# FPGA.net
KiCad netlist of a schematic drawn in Altium Designer
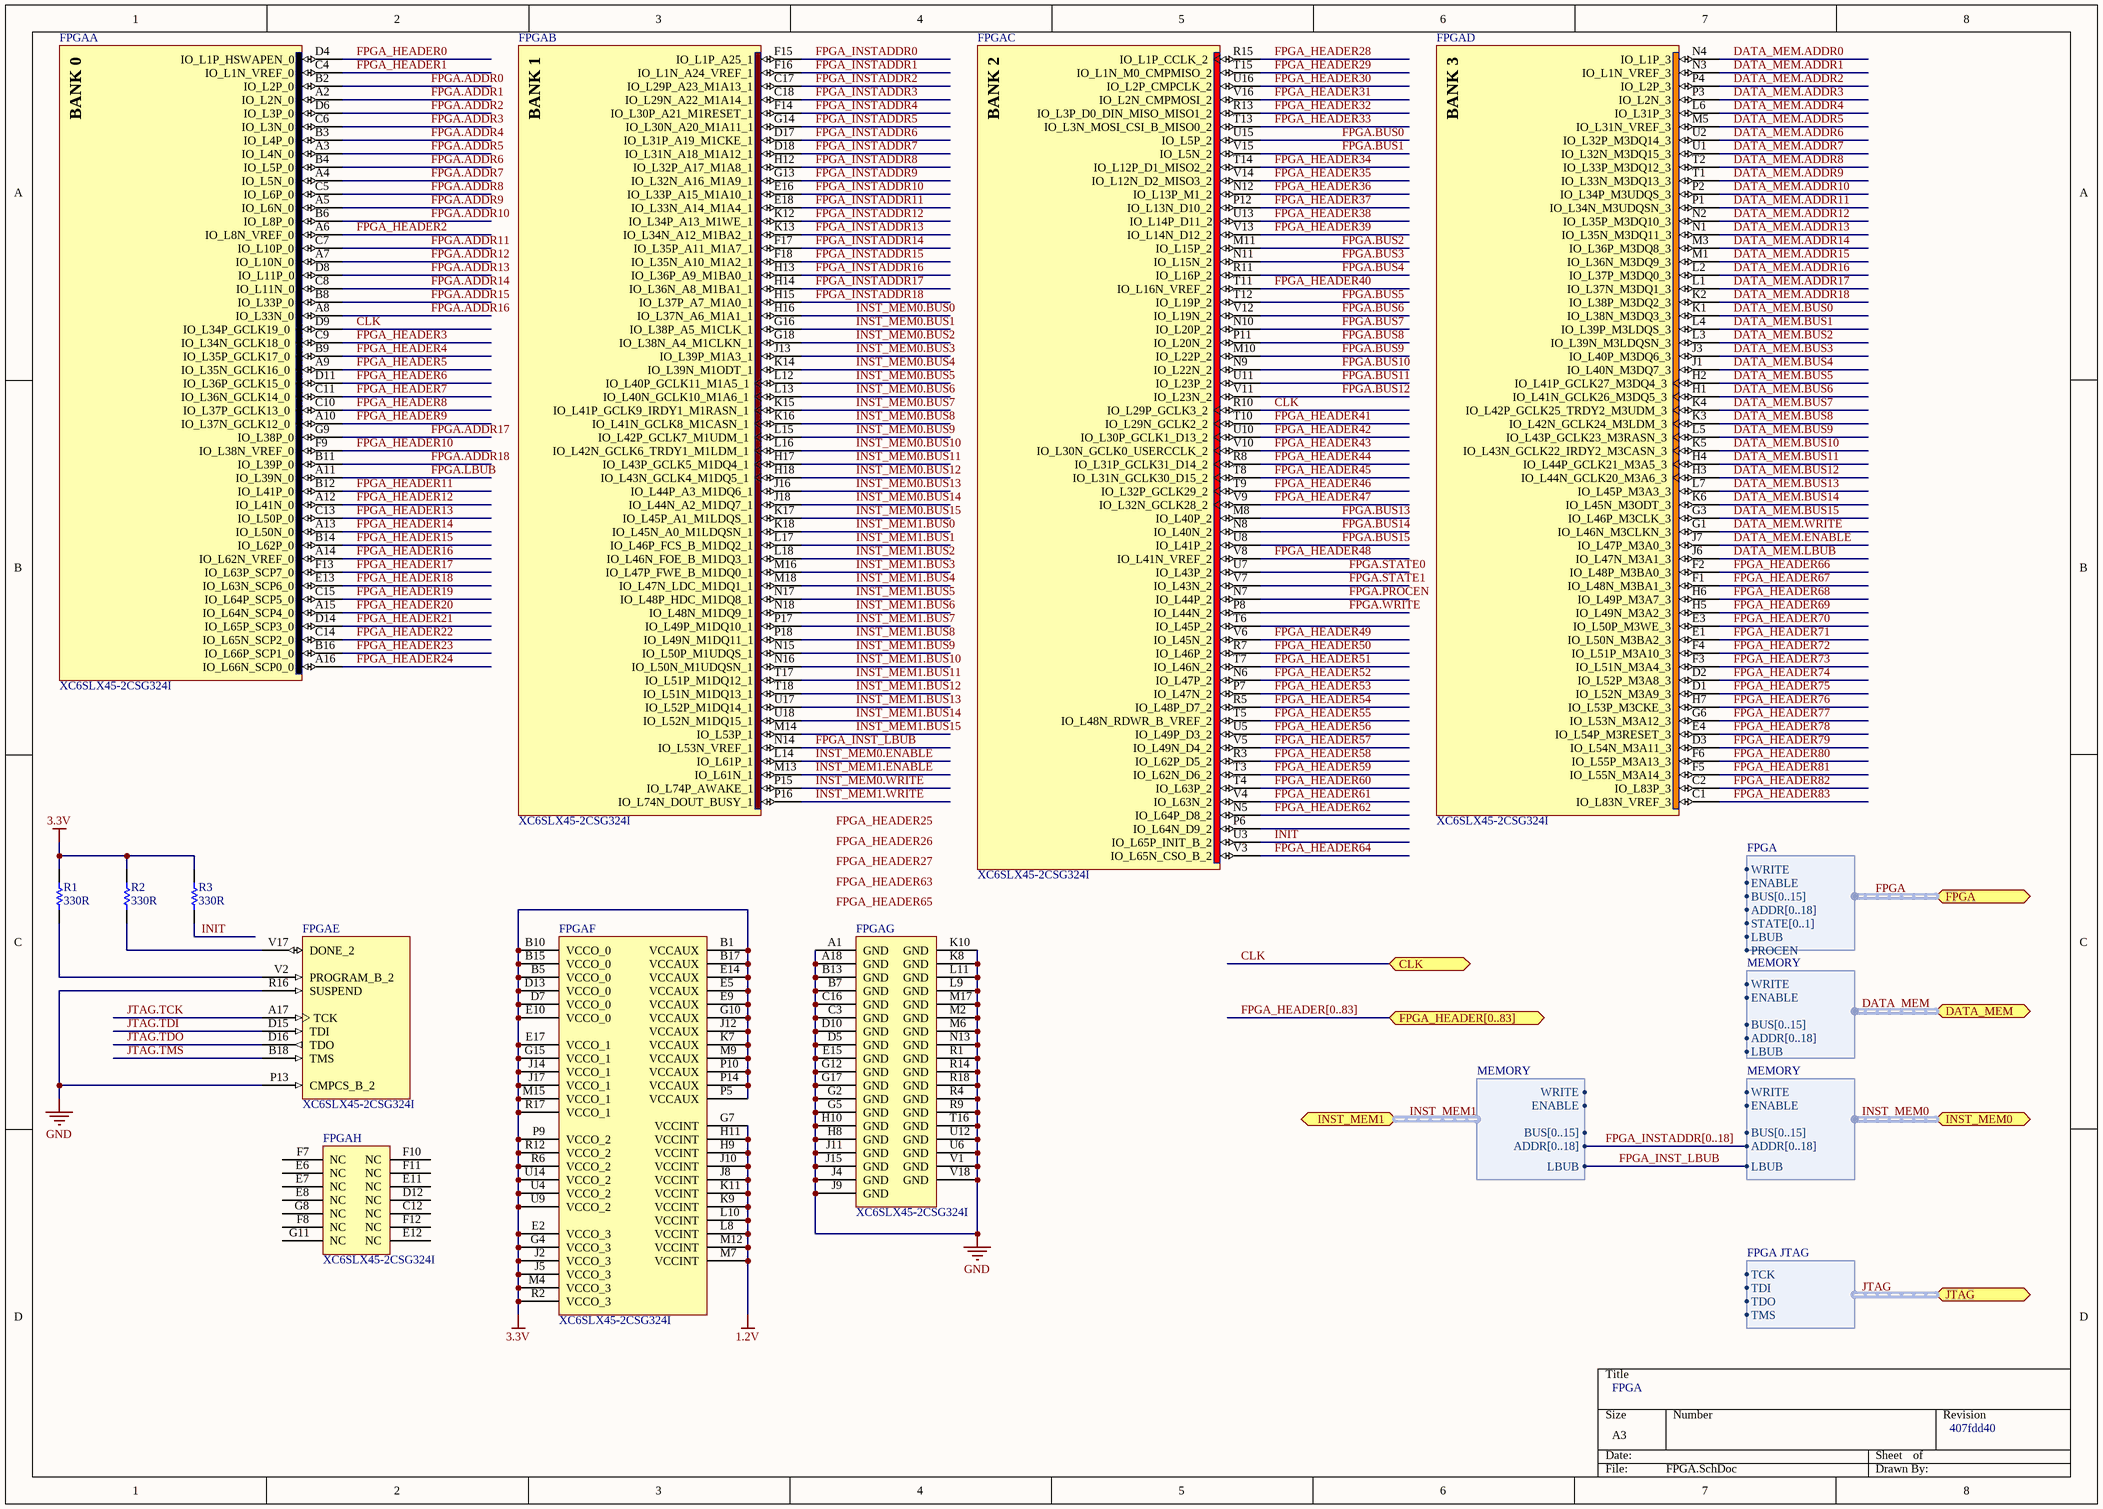
[diagram p0: FPGA.SchDoc]

(export (version "E")
  (design (tool "Eeschema 10.0.6"))
  (components
    (comp (ref "FPGA")
      (value "XC6SLX45-2CSG324I")
      (footprint "CSG324")
      (libsource (lib "Xilinx Spartan-6") (part "XC6SLX45-2CSG324I"))
    )
    (comp (ref "R1")
      (value "330R")
      (footprint "RESC1206(3216)_M")
      (description "330R 0.25W 5% 1206 (3216 Metric)  SMD")
      (fields (field (name "TOLERANCE") "5 %") (field (name "POWER") "0.25 W"))
      (libsource (lib "Altium Content Vault") (part "CMP-1014-00062-1"))
    )
    (comp (ref "R2")
      (value "330R")
      (footprint "RESC1206(3216)_M")
      (description "330R 0.25W 5% 1206 (3216 Metric)  SMD")
      (fields (field (name "TOLERANCE") "5 %") (field (name "POWER") "0.25 W"))
      (libsource (lib "Altium Content Vault") (part "CMP-1014-00062-1"))
    )
    (comp (ref "R3")
      (value "330R")
      (footprint "RESC1206(3216)_M")
      (description "330R 0.25W 5% 1206 (3216 Metric)  SMD")
      (fields (field (name "TOLERANCE") "5 %") (field (name "POWER") "0.25 W"))
      (libsource (lib "Altium Content Vault") (part "CMP-1014-00062-1"))
    )
  )
  (nets
    (net (code "7") (name "/CLK") (class "Default")
      (node (ref "FPGA") (pin "D9") (pinfunction "IO_L34P_GCLK19_0_D9") (pintype "bidirectional"))
      (node (ref "FPGA") (pin "R10") (pinfunction "IO_L29P_GCLK3_2_R10") (pintype "bidirectional"))
    )
    (net (code "8") (name "/DATA_MEM.ADDR0") (class "Default")
      (node (ref "FPGA") (pin "N4") (pinfunction "IO_L1P_3_N4") (pintype "bidirectional"))
    )
    (net (code "9") (name "/DATA_MEM.ADDR1") (class "Default")
      (node (ref "FPGA") (pin "N3") (pinfunction "IO_L1N_VREF_3_N3") (pintype "bidirectional"))
    )
    (net (code "10") (name "/DATA_MEM.ADDR2") (class "Default")
      (node (ref "FPGA") (pin "P4") (pinfunction "IO_L2P_3_P4") (pintype "bidirectional"))
    )
    (net (code "11") (name "/DATA_MEM.ADDR3") (class "Default")
      (node (ref "FPGA") (pin "P3") (pinfunction "IO_L2N_3_P3") (pintype "bidirectional"))
    )
    (net (code "12") (name "/DATA_MEM.ADDR4") (class "Default")
      (node (ref "FPGA") (pin "L6") (pinfunction "IO_L31P_3_L6") (pintype "bidirectional"))
    )
    (net (code "13") (name "/DATA_MEM.ADDR5") (class "Default")
      (node (ref "FPGA") (pin "M5") (pinfunction "IO_L31N_VREF_3_M5") (pintype "bidirectional"))
    )
    (net (code "14") (name "/DATA_MEM.ADDR6") (class "Default")
      (node (ref "FPGA") (pin "U2") (pinfunction "IO_L32P_M3DQ14_3_U2") (pintype "bidirectional"))
    )
    (net (code "15") (name "/DATA_MEM.ADDR7") (class "Default")
      (node (ref "FPGA") (pin "U1") (pinfunction "IO_L32N_M3DQ15_3_U1") (pintype "bidirectional"))
    )
    (net (code "16") (name "/DATA_MEM.ADDR8") (class "Default")
      (node (ref "FPGA") (pin "T2") (pinfunction "IO_L33P_M3DQ12_3_T2") (pintype "bidirectional"))
    )
    (net (code "17") (name "/DATA_MEM.ADDR9") (class "Default")
      (node (ref "FPGA") (pin "T1") (pinfunction "IO_L33N_M3DQ13_3_T1") (pintype "bidirectional"))
    )
    (net (code "18") (name "/DATA_MEM.ADDR10") (class "Default")
      (node (ref "FPGA") (pin "P2") (pinfunction "IO_L34P_M3UDQS_3_P2") (pintype "bidirectional"))
    )
    (net (code "19") (name "/DATA_MEM.ADDR11") (class "Default")
      (node (ref "FPGA") (pin "P1") (pinfunction "IO_L34N_M3UDQSN_3_P1") (pintype "bidirectional"))
    )
    (net (code "20") (name "/DATA_MEM.ADDR12") (class "Default")
      (node (ref "FPGA") (pin "N2") (pinfunction "IO_L35P_M3DQ10_3_N2") (pintype "bidirectional"))
    )
    (net (code "21") (name "/DATA_MEM.ADDR13") (class "Default")
      (node (ref "FPGA") (pin "N1") (pinfunction "IO_L35N_M3DQ11_3_N1") (pintype "bidirectional"))
    )
    (net (code "22") (name "/DATA_MEM.ADDR14") (class "Default")
      (node (ref "FPGA") (pin "M3") (pinfunction "IO_L36P_M3DQ8_3_M3") (pintype "bidirectional"))
    )
    (net (code "23") (name "/DATA_MEM.ADDR15") (class "Default")
      (node (ref "FPGA") (pin "M1") (pinfunction "IO_L36N_M3DQ9_3_M1") (pintype "bidirectional"))
    )
    (net (code "24") (name "/DATA_MEM.ADDR16") (class "Default")
      (node (ref "FPGA") (pin "L2") (pinfunction "IO_L37P_M3DQ0_3_L2") (pintype "bidirectional"))
    )
    (net (code "25") (name "/DATA_MEM.ADDR17") (class "Default")
      (node (ref "FPGA") (pin "L1") (pinfunction "IO_L37N_M3DQ1_3_L1") (pintype "bidirectional"))
    )
    (net (code "26") (name "/DATA_MEM.ADDR18") (class "Default")
      (node (ref "FPGA") (pin "K2") (pinfunction "IO_L38P_M3DQ2_3_K2") (pintype "bidirectional"))
    )
    (net (code "27") (name "/DATA_MEM.BUS0") (class "Default")
      (node (ref "FPGA") (pin "K1") (pinfunction "IO_L38N_M3DQ3_3_K1") (pintype "bidirectional"))
    )
    (net (code "28") (name "/DATA_MEM.BUS1") (class "Default")
      (node (ref "FPGA") (pin "L4") (pinfunction "IO_L39P_M3LDQS_3_L4") (pintype "bidirectional"))
    )
    (net (code "29") (name "/DATA_MEM.BUS2") (class "Default")
      (node (ref "FPGA") (pin "L3") (pinfunction "IO_L39N_M3LDQSN_3_L3") (pintype "bidirectional"))
    )
    (net (code "30") (name "/DATA_MEM.BUS3") (class "Default")
      (node (ref "FPGA") (pin "J3") (pinfunction "IO_L40P_M3DQ6_3_J3") (pintype "bidirectional"))
    )
    (net (code "31") (name "/DATA_MEM.BUS4") (class "Default")
      (node (ref "FPGA") (pin "J1") (pinfunction "IO_L40N_M3DQ7_3_J1") (pintype "bidirectional"))
    )
    (net (code "32") (name "/DATA_MEM.BUS5") (class "Default")
      (node (ref "FPGA") (pin "H2") (pinfunction "IO_L41P_GCLK27_M3DQ4_3_H2") (pintype "bidirectional"))
    )
    (net (code "33") (name "/DATA_MEM.BUS6") (class "Default")
      (node (ref "FPGA") (pin "H1") (pinfunction "IO_L41N_GCLK26_M3DQ5_3_H1") (pintype "bidirectional"))
    )
    (net (code "34") (name "/DATA_MEM.BUS7") (class "Default")
      (node (ref "FPGA") (pin "K4") (pinfunction "IO_L42P_GCLK25_TRDY2_M3UDM_3_K4") (pintype "bidirectional"))
    )
    (net (code "35") (name "/DATA_MEM.BUS8") (class "Default")
      (node (ref "FPGA") (pin "K3") (pinfunction "IO_L42N_GCLK24_M3LDM_3_K3") (pintype "bidirectional"))
    )
    (net (code "36") (name "/DATA_MEM.BUS9") (class "Default")
      (node (ref "FPGA") (pin "L5") (pinfunction "IO_L43P_GCLK23_M3RASN_3_L5") (pintype "bidirectional"))
    )
    (net (code "37") (name "/DATA_MEM.BUS10") (class "Default")
      (node (ref "FPGA") (pin "K5") (pinfunction "IO_L43N_GCLK22_IRDY2_M3CASN_3_K5") (pintype "bidirectional"))
    )
    (net (code "38") (name "/DATA_MEM.BUS11") (class "Default")
      (node (ref "FPGA") (pin "H4") (pinfunction "IO_L44P_GCLK21_M3A5_3_H4") (pintype "bidirectional"))
    )
    (net (code "39") (name "/DATA_MEM.BUS12") (class "Default")
      (node (ref "FPGA") (pin "H3") (pinfunction "IO_L44N_GCLK20_M3A6_3_H3") (pintype "bidirectional"))
    )
    (net (code "40") (name "/DATA_MEM.BUS13") (class "Default")
      (node (ref "FPGA") (pin "L7") (pinfunction "IO_L45P_M3A3_3_L7") (pintype "bidirectional"))
    )
    (net (code "41") (name "/DATA_MEM.BUS14") (class "Default")
      (node (ref "FPGA") (pin "K6") (pinfunction "IO_L45N_M3ODT_3_K6") (pintype "bidirectional"))
    )
    (net (code "42") (name "/DATA_MEM.BUS15") (class "Default")
      (node (ref "FPGA") (pin "G3") (pinfunction "IO_L46P_M3CLK_3_G3") (pintype "bidirectional"))
    )
    (net (code "43") (name "/DATA_MEM.ENABLE") (class "Default")
      (node (ref "FPGA") (pin "J7") (pinfunction "IO_L47P_M3A0_3_J7") (pintype "bidirectional"))
    )
    (net (code "44") (name "/DATA_MEM.LBUB") (class "Default")
      (node (ref "FPGA") (pin "J6") (pinfunction "IO_L47N_M3A1_3_J6") (pintype "bidirectional"))
    )
    (net (code "45") (name "/DATA_MEM.WRITE") (class "Default")
      (node (ref "FPGA") (pin "G1") (pinfunction "IO_L46N_M3CLKN_3_G1") (pintype "bidirectional"))
    )
    (net (code "47") (name "/FPGA.ADDR0") (class "Default")
      (node (ref "FPGA") (pin "B2") (pinfunction "IO_L2P_0_B2") (pintype "bidirectional"))
    )
    (net (code "48") (name "/FPGA.ADDR1") (class "Default")
      (node (ref "FPGA") (pin "A2") (pinfunction "IO_L2N_0_A2") (pintype "bidirectional"))
    )
    (net (code "49") (name "/FPGA.ADDR2") (class "Default")
      (node (ref "FPGA") (pin "D6") (pinfunction "IO_L3P_0_D6") (pintype "bidirectional"))
    )
    (net (code "50") (name "/FPGA.ADDR3") (class "Default")
      (node (ref "FPGA") (pin "C6") (pinfunction "IO_L3N_0_C6") (pintype "bidirectional"))
    )
    (net (code "51") (name "/FPGA.ADDR4") (class "Default")
      (node (ref "FPGA") (pin "B3") (pinfunction "IO_L4P_0_B3") (pintype "bidirectional"))
    )
    (net (code "52") (name "/FPGA.ADDR5") (class "Default")
      (node (ref "FPGA") (pin "A3") (pinfunction "IO_L4N_0_A3") (pintype "bidirectional"))
    )
    (net (code "53") (name "/FPGA.ADDR6") (class "Default")
      (node (ref "FPGA") (pin "B4") (pinfunction "IO_L5P_0_B4") (pintype "bidirectional"))
    )
    (net (code "54") (name "/FPGA.ADDR7") (class "Default")
      (node (ref "FPGA") (pin "A4") (pinfunction "IO_L5N_0_A4") (pintype "bidirectional"))
    )
    (net (code "55") (name "/FPGA.ADDR8") (class "Default")
      (node (ref "FPGA") (pin "C5") (pinfunction "IO_L6P_0_C5") (pintype "bidirectional"))
    )
    (net (code "56") (name "/FPGA.ADDR9") (class "Default")
      (node (ref "FPGA") (pin "A5") (pinfunction "IO_L6N_0_A5") (pintype "bidirectional"))
    )
    (net (code "57") (name "/FPGA.ADDR10") (class "Default")
      (node (ref "FPGA") (pin "B6") (pinfunction "IO_L8P_0_B6") (pintype "bidirectional"))
    )
    (net (code "58") (name "/FPGA.ADDR11") (class "Default")
      (node (ref "FPGA") (pin "C7") (pinfunction "IO_L10P_0_C7") (pintype "bidirectional"))
    )
    (net (code "59") (name "/FPGA.ADDR12") (class "Default")
      (node (ref "FPGA") (pin "A7") (pinfunction "IO_L10N_0_A7") (pintype "bidirectional"))
    )
    (net (code "60") (name "/FPGA.ADDR13") (class "Default")
      (node (ref "FPGA") (pin "D8") (pinfunction "IO_L11P_0_D8") (pintype "bidirectional"))
    )
    (net (code "61") (name "/FPGA.ADDR14") (class "Default")
      (node (ref "FPGA") (pin "C8") (pinfunction "IO_L11N_0_C8") (pintype "bidirectional"))
    )
    (net (code "62") (name "/FPGA.ADDR15") (class "Default")
      (node (ref "FPGA") (pin "B8") (pinfunction "IO_L33P_0_B8") (pintype "bidirectional"))
    )
    (net (code "63") (name "/FPGA.ADDR16") (class "Default")
      (node (ref "FPGA") (pin "A8") (pinfunction "IO_L33N_0_A8") (pintype "bidirectional"))
    )
    (net (code "64") (name "/FPGA.ADDR17") (class "Default")
      (node (ref "FPGA") (pin "G9") (pinfunction "IO_L38P_0_G9") (pintype "bidirectional"))
    )
    (net (code "65") (name "/FPGA.ADDR18") (class "Default")
      (node (ref "FPGA") (pin "B11") (pinfunction "IO_L39P_0_B11") (pintype "bidirectional"))
    )
    (net (code "66") (name "/FPGA.BUS0") (class "Default")
      (node (ref "FPGA") (pin "U15") (pinfunction "IO_L5P_2_U15") (pintype "bidirectional"))
    )
    (net (code "67") (name "/FPGA.BUS1") (class "Default")
      (node (ref "FPGA") (pin "V15") (pinfunction "IO_L5N_2_V15") (pintype "bidirectional"))
    )
    (net (code "68") (name "/FPGA.BUS2") (class "Default")
      (node (ref "FPGA") (pin "M11") (pinfunction "IO_L15P_2_M11") (pintype "bidirectional"))
    )
    (net (code "69") (name "/FPGA.BUS3") (class "Default")
      (node (ref "FPGA") (pin "N11") (pinfunction "IO_L15N_2_N11") (pintype "bidirectional"))
    )
    (net (code "70") (name "/FPGA.BUS4") (class "Default")
      (node (ref "FPGA") (pin "R11") (pinfunction "IO_L16P_2_R11") (pintype "bidirectional"))
    )
    (net (code "71") (name "/FPGA.BUS5") (class "Default")
      (node (ref "FPGA") (pin "T12") (pinfunction "IO_L19P_2_T12") (pintype "bidirectional"))
    )
    (net (code "72") (name "/FPGA.BUS6") (class "Default")
      (node (ref "FPGA") (pin "V12") (pinfunction "IO_L19N_2_V12") (pintype "bidirectional"))
    )
    (net (code "73") (name "/FPGA.BUS7") (class "Default")
      (node (ref "FPGA") (pin "N10") (pinfunction "IO_L20P_2_N10") (pintype "bidirectional"))
    )
    (net (code "74") (name "/FPGA.BUS8") (class "Default")
      (node (ref "FPGA") (pin "P11") (pinfunction "IO_L20N_2_P11") (pintype "bidirectional"))
    )
    (net (code "75") (name "/FPGA.BUS9") (class "Default")
      (node (ref "FPGA") (pin "M10") (pinfunction "IO_L22P_2_M10") (pintype "bidirectional"))
    )
    (net (code "76") (name "/FPGA.BUS10") (class "Default")
      (node (ref "FPGA") (pin "N9") (pinfunction "IO_L22N_2_N9") (pintype "bidirectional"))
    )
    (net (code "77") (name "/FPGA.BUS11") (class "Default")
      (node (ref "FPGA") (pin "U11") (pinfunction "IO_L23P_2_U11") (pintype "bidirectional"))
    )
    (net (code "78") (name "/FPGA.BUS12") (class "Default")
      (node (ref "FPGA") (pin "V11") (pinfunction "IO_L23N_2_V11") (pintype "bidirectional"))
    )
    (net (code "79") (name "/FPGA.BUS13") (class "Default")
      (node (ref "FPGA") (pin "M8") (pinfunction "IO_L40P_2_M8") (pintype "bidirectional"))
    )
    (net (code "80") (name "/FPGA.BUS14") (class "Default")
      (node (ref "FPGA") (pin "N8") (pinfunction "IO_L40N_2_N8") (pintype "bidirectional"))
    )
    (net (code "81") (name "/FPGA.BUS15") (class "Default")
      (node (ref "FPGA") (pin "U8") (pinfunction "IO_L41P_2_U8") (pintype "bidirectional"))
    )
    (net (code "82") (name "/FPGA.LBUB") (class "Default")
      (node (ref "FPGA") (pin "A11") (pinfunction "IO_L39N_0_A11") (pintype "bidirectional"))
    )
    (net (code "83") (name "/FPGA.PROCEN") (class "Default")
      (node (ref "FPGA") (pin "N7") (pinfunction "IO_L44P_2_N7") (pintype "bidirectional"))
    )
    (net (code "84") (name "/FPGA.STATE0") (class "Default")
      (node (ref "FPGA") (pin "U7") (pinfunction "IO_L43P_2_U7") (pintype "bidirectional"))
    )
    (net (code "85") (name "/FPGA.STATE1") (class "Default")
      (node (ref "FPGA") (pin "V7") (pinfunction "IO_L43N_2_V7") (pintype "bidirectional"))
    )
    (net (code "86") (name "/FPGA.WRITE") (class "Default")
      (node (ref "FPGA") (pin "P8") (pinfunction "IO_L44N_2_P8") (pintype "bidirectional"))
    )
    (net (code "87") (name "/FPGA_HEADER0") (class "Default")
      (node (ref "FPGA") (pin "D4") (pinfunction "IO_L1P_HSWAPEN_0_D4") (pintype "bidirectional"))
    )
    (net (code "88") (name "/FPGA_HEADER1") (class "Default")
      (node (ref "FPGA") (pin "C4") (pinfunction "IO_L1N_VREF_0_C4") (pintype "bidirectional"))
    )
    (net (code "89") (name "/FPGA_HEADER2") (class "Default")
      (node (ref "FPGA") (pin "A6") (pinfunction "IO_L8N_VREF_0_A6") (pintype "bidirectional"))
    )
    (net (code "90") (name "/FPGA_HEADER3") (class "Default")
      (node (ref "FPGA") (pin "C9") (pinfunction "IO_L34N_GCLK18_0_C9") (pintype "bidirectional"))
    )
    (net (code "91") (name "/FPGA_HEADER4") (class "Default")
      (node (ref "FPGA") (pin "B9") (pinfunction "IO_L35P_GCLK17_0_B9") (pintype "bidirectional"))
    )
    (net (code "92") (name "/FPGA_HEADER5") (class "Default")
      (node (ref "FPGA") (pin "A9") (pinfunction "IO_L35N_GCLK16_0_A9") (pintype "bidirectional"))
    )
    (net (code "93") (name "/FPGA_HEADER6") (class "Default")
      (node (ref "FPGA") (pin "D11") (pinfunction "IO_L36P_GCLK15_0_D11") (pintype "bidirectional"))
    )
    (net (code "94") (name "/FPGA_HEADER7") (class "Default")
      (node (ref "FPGA") (pin "C11") (pinfunction "IO_L36N_GCLK14_0_C11") (pintype "bidirectional"))
    )
    (net (code "95") (name "/FPGA_HEADER8") (class "Default")
      (node (ref "FPGA") (pin "C10") (pinfunction "IO_L37P_GCLK13_0_C10") (pintype "bidirectional"))
    )
    (net (code "96") (name "/FPGA_HEADER9") (class "Default")
      (node (ref "FPGA") (pin "A10") (pinfunction "IO_L37N_GCLK12_0_A10") (pintype "bidirectional"))
    )
    (net (code "97") (name "/FPGA_HEADER10") (class "Default")
      (node (ref "FPGA") (pin "F9") (pinfunction "IO_L38N_VREF_0_F9") (pintype "bidirectional"))
    )
    (net (code "98") (name "/FPGA_HEADER11") (class "Default")
      (node (ref "FPGA") (pin "B12") (pinfunction "IO_L41P_0_B12") (pintype "bidirectional"))
    )
    (net (code "99") (name "/FPGA_HEADER12") (class "Default")
      (node (ref "FPGA") (pin "A12") (pinfunction "IO_L41N_0_A12") (pintype "bidirectional"))
    )
    (net (code "100") (name "/FPGA_HEADER13") (class "Default")
      (node (ref "FPGA") (pin "C13") (pinfunction "IO_L50P_0_C13") (pintype "bidirectional"))
    )
    (net (code "101") (name "/FPGA_HEADER14") (class "Default")
      (node (ref "FPGA") (pin "A13") (pinfunction "IO_L50N_0_A13") (pintype "bidirectional"))
    )
    (net (code "102") (name "/FPGA_HEADER15") (class "Default")
      (node (ref "FPGA") (pin "B14") (pinfunction "IO_L62P_0_B14") (pintype "bidirectional"))
    )
    (net (code "103") (name "/FPGA_HEADER16") (class "Default")
      (node (ref "FPGA") (pin "A14") (pinfunction "IO_L62N_VREF_0_A14") (pintype "bidirectional"))
    )
    (net (code "104") (name "/FPGA_HEADER17") (class "Default")
      (node (ref "FPGA") (pin "F13") (pinfunction "IO_L63P_SCP7_0_F13") (pintype "bidirectional"))
    )
    (net (code "105") (name "/FPGA_HEADER18") (class "Default")
      (node (ref "FPGA") (pin "E13") (pinfunction "IO_L63N_SCP6_0_E13") (pintype "bidirectional"))
    )
    (net (code "106") (name "/FPGA_HEADER19") (class "Default")
      (node (ref "FPGA") (pin "C15") (pinfunction "IO_L64P_SCP5_0_C15") (pintype "bidirectional"))
    )
    (net (code "107") (name "/FPGA_HEADER20") (class "Default")
      (node (ref "FPGA") (pin "A15") (pinfunction "IO_L64N_SCP4_0_A15") (pintype "bidirectional"))
    )
    (net (code "108") (name "/FPGA_HEADER21") (class "Default")
      (node (ref "FPGA") (pin "D14") (pinfunction "IO_L65P_SCP3_0_D14") (pintype "bidirectional"))
    )
    (net (code "109") (name "/FPGA_HEADER22") (class "Default")
      (node (ref "FPGA") (pin "C14") (pinfunction "IO_L65N_SCP2_0_C14") (pintype "bidirectional"))
    )
    (net (code "110") (name "/FPGA_HEADER23") (class "Default")
      (node (ref "FPGA") (pin "B16") (pinfunction "IO_L66P_SCP1_0_B16") (pintype "bidirectional"))
    )
    (net (code "111") (name "/FPGA_HEADER24") (class "Default")
      (node (ref "FPGA") (pin "A16") (pinfunction "IO_L66N_SCP0_0_A16") (pintype "bidirectional"))
    )
    (net (code "115") (name "/FPGA_HEADER28") (class "Default")
      (node (ref "FPGA") (pin "R15") (pinfunction "IO_L1P_CCLK_2_R15") (pintype "bidirectional"))
    )
    (net (code "116") (name "/FPGA_HEADER29") (class "Default")
      (node (ref "FPGA") (pin "T15") (pinfunction "IO_L1N_M0_CMPMISO_2_T15") (pintype "bidirectional"))
    )
    (net (code "117") (name "/FPGA_HEADER30") (class "Default")
      (node (ref "FPGA") (pin "U16") (pinfunction "IO_L2P_CMPCLK_2_U16") (pintype "bidirectional"))
    )
    (net (code "118") (name "/FPGA_HEADER31") (class "Default")
      (node (ref "FPGA") (pin "V16") (pinfunction "IO_L2N_CMPMOSI_2_V16") (pintype "bidirectional"))
    )
    (net (code "119") (name "/FPGA_HEADER32") (class "Default")
      (node (ref "FPGA") (pin "R13") (pinfunction "IO_L3P_D0_DIN_MISO_MISO1_2_R13") (pintype "bidirectional"))
    )
    (net (code "120") (name "/FPGA_HEADER33") (class "Default")
      (node (ref "FPGA") (pin "T13") (pinfunction "IO_L3N_MOSI_CSI_B_MISO0_2_T13") (pintype "bidirectional"))
    )
    (net (code "121") (name "/FPGA_HEADER34") (class "Default")
      (node (ref "FPGA") (pin "T14") (pinfunction "IO_L12P_D1_MISO2_2_T14") (pintype "bidirectional"))
    )
    (net (code "122") (name "/FPGA_HEADER35") (class "Default")
      (node (ref "FPGA") (pin "V14") (pinfunction "IO_L12N_D2_MISO3_2_V14") (pintype "bidirectional"))
    )
    (net (code "123") (name "/FPGA_HEADER36") (class "Default")
      (node (ref "FPGA") (pin "N12") (pinfunction "IO_L13P_M1_2_N12") (pintype "bidirectional"))
    )
    (net (code "124") (name "/FPGA_HEADER37") (class "Default")
      (node (ref "FPGA") (pin "P12") (pinfunction "IO_L13N_D10_2_P12") (pintype "bidirectional"))
    )
    (net (code "125") (name "/FPGA_HEADER38") (class "Default")
      (node (ref "FPGA") (pin "U13") (pinfunction "IO_L14P_D11_2_U13") (pintype "bidirectional"))
    )
    (net (code "126") (name "/FPGA_HEADER39") (class "Default")
      (node (ref "FPGA") (pin "V13") (pinfunction "IO_L14N_D12_2_V13") (pintype "bidirectional"))
    )
    (net (code "127") (name "/FPGA_HEADER40") (class "Default")
      (node (ref "FPGA") (pin "T11") (pinfunction "IO_L16N_VREF_2_T11") (pintype "bidirectional"))
    )
    (net (code "128") (name "/FPGA_HEADER41") (class "Default")
      (node (ref "FPGA") (pin "T10") (pinfunction "IO_L29N_GCLK2_2_T10") (pintype "bidirectional"))
    )
    (net (code "129") (name "/FPGA_HEADER42") (class "Default")
      (node (ref "FPGA") (pin "U10") (pinfunction "IO_L30P_GCLK1_D13_2_U10") (pintype "bidirectional"))
    )
    (net (code "130") (name "/FPGA_HEADER43") (class "Default")
      (node (ref "FPGA") (pin "V10") (pinfunction "IO_L30N_GCLK0_USERCCLK_2_V10") (pintype "bidirectional"))
    )
    (net (code "131") (name "/FPGA_HEADER44") (class "Default")
      (node (ref "FPGA") (pin "R8") (pinfunction "IO_L31P_GCLK31_D14_2_R8") (pintype "bidirectional"))
    )
    (net (code "132") (name "/FPGA_HEADER45") (class "Default")
      (node (ref "FPGA") (pin "T8") (pinfunction "IO_L31N_GCLK30_D15_2_T8") (pintype "bidirectional"))
    )
    (net (code "133") (name "/FPGA_HEADER46") (class "Default")
      (node (ref "FPGA") (pin "T9") (pinfunction "IO_L32P_GCLK29_2_T9") (pintype "bidirectional"))
    )
    (net (code "134") (name "/FPGA_HEADER47") (class "Default")
      (node (ref "FPGA") (pin "V9") (pinfunction "IO_L32N_GCLK28_2_V9") (pintype "bidirectional"))
    )
    (net (code "135") (name "/FPGA_HEADER48") (class "Default")
      (node (ref "FPGA") (pin "V8") (pinfunction "IO_L41N_VREF_2_V8") (pintype "bidirectional"))
    )
    (net (code "136") (name "/FPGA_HEADER49") (class "Default")
      (node (ref "FPGA") (pin "V6") (pinfunction "IO_L45N_2_V6") (pintype "bidirectional"))
    )
    (net (code "137") (name "/FPGA_HEADER50") (class "Default")
      (node (ref "FPGA") (pin "R7") (pinfunction "IO_L46P_2_R7") (pintype "bidirectional"))
    )
    (net (code "138") (name "/FPGA_HEADER51") (class "Default")
      (node (ref "FPGA") (pin "T7") (pinfunction "IO_L46N_2_T7") (pintype "bidirectional"))
    )
    (net (code "139") (name "/FPGA_HEADER52") (class "Default")
      (node (ref "FPGA") (pin "N6") (pinfunction "IO_L47P_2_N6") (pintype "bidirectional"))
    )
    (net (code "140") (name "/FPGA_HEADER53") (class "Default")
      (node (ref "FPGA") (pin "P7") (pinfunction "IO_L47N_2_P7") (pintype "bidirectional"))
    )
    (net (code "141") (name "/FPGA_HEADER54") (class "Default")
      (node (ref "FPGA") (pin "R5") (pinfunction "IO_L48P_D7_2_R5") (pintype "bidirectional"))
    )
    (net (code "142") (name "/FPGA_HEADER55") (class "Default")
      (node (ref "FPGA") (pin "T5") (pinfunction "IO_L48N_RDWR_B_VREF_2_T5") (pintype "bidirectional"))
    )
    (net (code "143") (name "/FPGA_HEADER56") (class "Default")
      (node (ref "FPGA") (pin "U5") (pinfunction "IO_L49P_D3_2_U5") (pintype "bidirectional"))
    )
    (net (code "144") (name "/FPGA_HEADER57") (class "Default")
      (node (ref "FPGA") (pin "V5") (pinfunction "IO_L49N_D4_2_V5") (pintype "bidirectional"))
    )
    (net (code "145") (name "/FPGA_HEADER58") (class "Default")
      (node (ref "FPGA") (pin "R3") (pinfunction "IO_L62P_D5_2_R3") (pintype "bidirectional"))
    )
    (net (code "146") (name "/FPGA_HEADER59") (class "Default")
      (node (ref "FPGA") (pin "T3") (pinfunction "IO_L62N_D6_2_T3") (pintype "bidirectional"))
    )
    (net (code "147") (name "/FPGA_HEADER60") (class "Default")
      (node (ref "FPGA") (pin "T4") (pinfunction "IO_L63P_2_T4") (pintype "bidirectional"))
    )
    (net (code "148") (name "/FPGA_HEADER61") (class "Default")
      (node (ref "FPGA") (pin "V4") (pinfunction "IO_L63N_2_V4") (pintype "bidirectional"))
    )
    (net (code "149") (name "/FPGA_HEADER62") (class "Default")
      (node (ref "FPGA") (pin "N5") (pinfunction "IO_L64P_D8_2_N5") (pintype "bidirectional"))
    )
    (net (code "151") (name "/FPGA_HEADER64") (class "Default")
      (node (ref "FPGA") (pin "V3") (pinfunction "IO_L65N_CSO_B_2_V3") (pintype "bidirectional"))
    )
    (net (code "153") (name "/FPGA_HEADER66") (class "Default")
      (node (ref "FPGA") (pin "F2") (pinfunction "IO_L48P_M3BA0_3_F2") (pintype "bidirectional"))
    )
    (net (code "154") (name "/FPGA_HEADER67") (class "Default")
      (node (ref "FPGA") (pin "F1") (pinfunction "IO_L48N_M3BA1_3_F1") (pintype "bidirectional"))
    )
    (net (code "155") (name "/FPGA_HEADER68") (class "Default")
      (node (ref "FPGA") (pin "H6") (pinfunction "IO_L49P_M3A7_3_H6") (pintype "bidirectional"))
    )
    (net (code "156") (name "/FPGA_HEADER69") (class "Default")
      (node (ref "FPGA") (pin "H5") (pinfunction "IO_L49N_M3A2_3_H5") (pintype "bidirectional"))
    )
    (net (code "157") (name "/FPGA_HEADER70") (class "Default")
      (node (ref "FPGA") (pin "E3") (pinfunction "IO_L50P_M3WE_3_E3") (pintype "bidirectional"))
    )
    (net (code "158") (name "/FPGA_HEADER71") (class "Default")
      (node (ref "FPGA") (pin "E1") (pinfunction "IO_L50N_M3BA2_3_E1") (pintype "bidirectional"))
    )
    (net (code "159") (name "/FPGA_HEADER72") (class "Default")
      (node (ref "FPGA") (pin "F4") (pinfunction "IO_L51P_M3A10_3_F4") (pintype "bidirectional"))
    )
    (net (code "160") (name "/FPGA_HEADER73") (class "Default")
      (node (ref "FPGA") (pin "F3") (pinfunction "IO_L51N_M3A4_3_F3") (pintype "bidirectional"))
    )
    (net (code "161") (name "/FPGA_HEADER74") (class "Default")
      (node (ref "FPGA") (pin "D2") (pinfunction "IO_L52P_M3A8_3_D2") (pintype "bidirectional"))
    )
    (net (code "162") (name "/FPGA_HEADER75") (class "Default")
      (node (ref "FPGA") (pin "D1") (pinfunction "IO_L52N_M3A9_3_D1") (pintype "bidirectional"))
    )
    (net (code "163") (name "/FPGA_HEADER76") (class "Default")
      (node (ref "FPGA") (pin "H7") (pinfunction "IO_L53P_M3CKE_3_H7") (pintype "bidirectional"))
    )
    (net (code "164") (name "/FPGA_HEADER77") (class "Default")
      (node (ref "FPGA") (pin "G6") (pinfunction "IO_L53N_M3A12_3_G6") (pintype "bidirectional"))
    )
    (net (code "165") (name "/FPGA_HEADER78") (class "Default")
      (node (ref "FPGA") (pin "E4") (pinfunction "IO_L54P_M3RESET_3_E4") (pintype "bidirectional"))
    )
    (net (code "166") (name "/FPGA_HEADER79") (class "Default")
      (node (ref "FPGA") (pin "D3") (pinfunction "IO_L54N_M3A11_3_D3") (pintype "bidirectional"))
    )
    (net (code "167") (name "/FPGA_HEADER80") (class "Default")
      (node (ref "FPGA") (pin "F6") (pinfunction "IO_L55P_M3A13_3_F6") (pintype "bidirectional"))
    )
    (net (code "168") (name "/FPGA_HEADER81") (class "Default")
      (node (ref "FPGA") (pin "F5") (pinfunction "IO_L55N_M3A14_3_F5") (pintype "bidirectional"))
    )
    (net (code "169") (name "/FPGA_HEADER82") (class "Default")
      (node (ref "FPGA") (pin "C2") (pinfunction "IO_L83P_3_C2") (pintype "bidirectional"))
    )
    (net (code "170") (name "/FPGA_HEADER83") (class "Default")
      (node (ref "FPGA") (pin "C1") (pinfunction "IO_L83N_VREF_3_C1") (pintype "bidirectional"))
    )
    (net (code "172") (name "/FPGA_INSTADDR0") (class "Default")
      (node (ref "FPGA") (pin "F15") (pinfunction "IO_L1P_A25_1_F15") (pintype "bidirectional"))
    )
    (net (code "173") (name "/FPGA_INSTADDR1") (class "Default")
      (node (ref "FPGA") (pin "F16") (pinfunction "IO_L1N_A24_VREF_1_F16") (pintype "bidirectional"))
    )
    (net (code "174") (name "/FPGA_INSTADDR2") (class "Default")
      (node (ref "FPGA") (pin "C17") (pinfunction "IO_L29P_A23_M1A13_1_C17") (pintype "bidirectional"))
    )
    (net (code "175") (name "/FPGA_INSTADDR3") (class "Default")
      (node (ref "FPGA") (pin "C18") (pinfunction "IO_L29N_A22_M1A14_1_C18") (pintype "bidirectional"))
    )
    (net (code "176") (name "/FPGA_INSTADDR4") (class "Default")
      (node (ref "FPGA") (pin "F14") (pinfunction "IO_L30P_A21_M1RESET_1_F14") (pintype "bidirectional"))
    )
    (net (code "177") (name "/FPGA_INSTADDR5") (class "Default")
      (node (ref "FPGA") (pin "G14") (pinfunction "IO_L30N_A20_M1A11_1_G14") (pintype "bidirectional"))
    )
    (net (code "178") (name "/FPGA_INSTADDR6") (class "Default")
      (node (ref "FPGA") (pin "D17") (pinfunction "IO_L31P_A19_M1CKE_1_D17") (pintype "bidirectional"))
    )
    (net (code "179") (name "/FPGA_INSTADDR7") (class "Default")
      (node (ref "FPGA") (pin "D18") (pinfunction "IO_L31N_A18_M1A12_1_D18") (pintype "bidirectional"))
    )
    (net (code "180") (name "/FPGA_INSTADDR8") (class "Default")
      (node (ref "FPGA") (pin "H12") (pinfunction "IO_L32P_A17_M1A8_1_H12") (pintype "bidirectional"))
    )
    (net (code "181") (name "/FPGA_INSTADDR9") (class "Default")
      (node (ref "FPGA") (pin "G13") (pinfunction "IO_L32N_A16_M1A9_1_G13") (pintype "bidirectional"))
    )
    (net (code "182") (name "/FPGA_INSTADDR10") (class "Default")
      (node (ref "FPGA") (pin "E16") (pinfunction "IO_L33P_A15_M1A10_1_E16") (pintype "bidirectional"))
    )
    (net (code "183") (name "/FPGA_INSTADDR11") (class "Default")
      (node (ref "FPGA") (pin "E18") (pinfunction "IO_L33N_A14_M1A4_1_E18") (pintype "bidirectional"))
    )
    (net (code "184") (name "/FPGA_INSTADDR12") (class "Default")
      (node (ref "FPGA") (pin "K12") (pinfunction "IO_L34P_A13_M1WE_1_K12") (pintype "bidirectional"))
    )
    (net (code "185") (name "/FPGA_INSTADDR13") (class "Default")
      (node (ref "FPGA") (pin "K13") (pinfunction "IO_L34N_A12_M1BA2_1_K13") (pintype "bidirectional"))
    )
    (net (code "186") (name "/FPGA_INSTADDR14") (class "Default")
      (node (ref "FPGA") (pin "F17") (pinfunction "IO_L35P_A11_M1A7_1_F17") (pintype "bidirectional"))
    )
    (net (code "187") (name "/FPGA_INSTADDR15") (class "Default")
      (node (ref "FPGA") (pin "F18") (pinfunction "IO_L35N_A10_M1A2_1_F18") (pintype "bidirectional"))
    )
    (net (code "188") (name "/FPGA_INSTADDR16") (class "Default")
      (node (ref "FPGA") (pin "H13") (pinfunction "IO_L36P_A9_M1BA0_1_H13") (pintype "bidirectional"))
    )
    (net (code "189") (name "/FPGA_INSTADDR17") (class "Default")
      (node (ref "FPGA") (pin "H14") (pinfunction "IO_L36N_A8_M1BA1_1_H14") (pintype "bidirectional"))
    )
    (net (code "190") (name "/FPGA_INSTADDR18") (class "Default")
      (node (ref "FPGA") (pin "H15") (pinfunction "IO_L37P_A7_M1A0_1_H15") (pintype "bidirectional"))
    )
    (net (code "192") (name "/FPGA_INST_LBUB") (class "Default")
      (node (ref "FPGA") (pin "N14") (pinfunction "IO_L53N_VREF_1_N14") (pintype "bidirectional"))
    )
    (net (code "194") (name "/INIT") (class "Default")
      (node (ref "FPGA") (pin "U3") (pinfunction "IO_L65P_INIT_B_2_U3") (pintype "bidirectional"))
      (node (ref "R3") (pin "1") (pinfunction "1_1") (pintype "passive"))
    )
    (net (code "195") (name "/INST_MEM0.BUS0") (class "Default")
      (node (ref "FPGA") (pin "H16") (pinfunction "IO_L37N_A6_M1A1_1_H16") (pintype "bidirectional"))
    )
    (net (code "196") (name "/INST_MEM0.BUS1") (class "Default")
      (node (ref "FPGA") (pin "G16") (pinfunction "IO_L38P_A5_M1CLK_1_G16") (pintype "bidirectional"))
    )
    (net (code "197") (name "/INST_MEM0.BUS2") (class "Default")
      (node (ref "FPGA") (pin "G18") (pinfunction "IO_L38N_A4_M1CLKN_1_G18") (pintype "bidirectional"))
    )
    (net (code "198") (name "/INST_MEM0.BUS3") (class "Default")
      (node (ref "FPGA") (pin "J13") (pinfunction "IO_L39P_M1A3_1_J13") (pintype "bidirectional"))
    )
    (net (code "199") (name "/INST_MEM0.BUS4") (class "Default")
      (node (ref "FPGA") (pin "K14") (pinfunction "IO_L39N_M1ODT_1_K14") (pintype "bidirectional"))
    )
    (net (code "200") (name "/INST_MEM0.BUS5") (class "Default")
      (node (ref "FPGA") (pin "L12") (pinfunction "IO_L40P_GCLK11_M1A5_1_L12") (pintype "bidirectional"))
    )
    (net (code "201") (name "/INST_MEM0.BUS6") (class "Default")
      (node (ref "FPGA") (pin "L13") (pinfunction "IO_L40N_GCLK10_M1A6_1_L13") (pintype "bidirectional"))
    )
    (net (code "202") (name "/INST_MEM0.BUS7") (class "Default")
      (node (ref "FPGA") (pin "K15") (pinfunction "IO_L41P_GCLK9_IRDY1_M1RASN_1_K15") (pintype "bidirectional"))
    )
    (net (code "203") (name "/INST_MEM0.BUS8") (class "Default")
      (node (ref "FPGA") (pin "K16") (pinfunction "IO_L41N_GCLK8_M1CASN_1_K16") (pintype "bidirectional"))
    )
    (net (code "204") (name "/INST_MEM0.BUS9") (class "Default")
      (node (ref "FPGA") (pin "L15") (pinfunction "IO_L42P_GCLK7_M1UDM_1_L15") (pintype "bidirectional"))
    )
    (net (code "205") (name "/INST_MEM0.BUS10") (class "Default")
      (node (ref "FPGA") (pin "L16") (pinfunction "IO_L42N_GCLK6_TRDY1_M1LDM_1_L16") (pintype "bidirectional"))
    )
    (net (code "206") (name "/INST_MEM0.BUS11") (class "Default")
      (node (ref "FPGA") (pin "H17") (pinfunction "IO_L43P_GCLK5_M1DQ4_1_H17") (pintype "bidirectional"))
    )
    (net (code "207") (name "/INST_MEM0.BUS12") (class "Default")
      (node (ref "FPGA") (pin "H18") (pinfunction "IO_L43N_GCLK4_M1DQ5_1_H18") (pintype "bidirectional"))
    )
    (net (code "208") (name "/INST_MEM0.BUS13") (class "Default")
      (node (ref "FPGA") (pin "J16") (pinfunction "IO_L44P_A3_M1DQ6_1_J16") (pintype "bidirectional"))
    )
    (net (code "209") (name "/INST_MEM0.BUS14") (class "Default")
      (node (ref "FPGA") (pin "J18") (pinfunction "IO_L44N_A2_M1DQ7_1_J18") (pintype "bidirectional"))
    )
    (net (code "210") (name "/INST_MEM0.BUS15") (class "Default")
      (node (ref "FPGA") (pin "K17") (pinfunction "IO_L45P_A1_M1LDQS_1_K17") (pintype "bidirectional"))
    )
    (net (code "211") (name "/INST_MEM0.ENABLE") (class "Default")
      (node (ref "FPGA") (pin "L14") (pinfunction "IO_L61P_1_L14") (pintype "bidirectional"))
    )
    (net (code "212") (name "/INST_MEM0.WRITE") (class "Default")
      (node (ref "FPGA") (pin "P15") (pinfunction "IO_L74P_AWAKE_1_P15") (pintype "bidirectional"))
    )
    (net (code "214") (name "/INST_MEM1.BUS0") (class "Default")
      (node (ref "FPGA") (pin "K18") (pinfunction "IO_L45N_A0_M1LDQSN_1_K18") (pintype "bidirectional"))
    )
    (net (code "215") (name "/INST_MEM1.BUS1") (class "Default")
      (node (ref "FPGA") (pin "L17") (pinfunction "IO_L46P_FCS_B_M1DQ2_1_L17") (pintype "bidirectional"))
    )
    (net (code "216") (name "/INST_MEM1.BUS2") (class "Default")
      (node (ref "FPGA") (pin "L18") (pinfunction "IO_L46N_FOE_B_M1DQ3_1_L18") (pintype "bidirectional"))
    )
    (net (code "217") (name "/INST_MEM1.BUS3") (class "Default")
      (node (ref "FPGA") (pin "M16") (pinfunction "IO_L47P_FWE_B_M1DQ0_1_M16") (pintype "bidirectional"))
    )
    (net (code "218") (name "/INST_MEM1.BUS4") (class "Default")
      (node (ref "FPGA") (pin "M18") (pinfunction "IO_L47N_LDC_M1DQ1_1_M18") (pintype "bidirectional"))
    )
    (net (code "219") (name "/INST_MEM1.BUS5") (class "Default")
      (node (ref "FPGA") (pin "N17") (pinfunction "IO_L48P_HDC_M1DQ8_1_N17") (pintype "bidirectional"))
    )
    (net (code "220") (name "/INST_MEM1.BUS6") (class "Default")
      (node (ref "FPGA") (pin "N18") (pinfunction "IO_L48N_M1DQ9_1_N18") (pintype "bidirectional"))
    )
    (net (code "221") (name "/INST_MEM1.BUS7") (class "Default")
      (node (ref "FPGA") (pin "P17") (pinfunction "IO_L49P_M1DQ10_1_P17") (pintype "bidirectional"))
    )
    (net (code "222") (name "/INST_MEM1.BUS8") (class "Default")
      (node (ref "FPGA") (pin "P18") (pinfunction "IO_L49N_M1DQ11_1_P18") (pintype "bidirectional"))
    )
    (net (code "223") (name "/INST_MEM1.BUS9") (class "Default")
      (node (ref "FPGA") (pin "N15") (pinfunction "IO_L50P_M1UDQS_1_N15") (pintype "bidirectional"))
    )
    (net (code "224") (name "/INST_MEM1.BUS10") (class "Default")
      (node (ref "FPGA") (pin "N16") (pinfunction "IO_L50N_M1UDQSN_1_N16") (pintype "bidirectional"))
    )
    (net (code "225") (name "/INST_MEM1.BUS11") (class "Default")
      (node (ref "FPGA") (pin "T17") (pinfunction "IO_L51P_M1DQ12_1_T17") (pintype "bidirectional"))
    )
    (net (code "226") (name "/INST_MEM1.BUS12") (class "Default")
      (node (ref "FPGA") (pin "T18") (pinfunction "IO_L51N_M1DQ13_1_T18") (pintype "bidirectional"))
    )
    (net (code "227") (name "/INST_MEM1.BUS13") (class "Default")
      (node (ref "FPGA") (pin "U17") (pinfunction "IO_L52P_M1DQ14_1_U17") (pintype "bidirectional"))
    )
    (net (code "228") (name "/INST_MEM1.BUS14") (class "Default")
      (node (ref "FPGA") (pin "U18") (pinfunction "IO_L52N_M1DQ15_1_U18") (pintype "bidirectional"))
    )
    (net (code "229") (name "/INST_MEM1.BUS15") (class "Default")
      (node (ref "FPGA") (pin "M14") (pinfunction "IO_L53P_1_M14") (pintype "bidirectional"))
    )
    (net (code "230") (name "/INST_MEM1.ENABLE") (class "Default")
      (node (ref "FPGA") (pin "M13") (pinfunction "IO_L61N_1_M13") (pintype "bidirectional"))
    )
    (net (code "231") (name "/INST_MEM1.WRITE") (class "Default")
      (node (ref "FPGA") (pin "P16") (pinfunction "IO_L74N_DOUT_BUSY_1_P16") (pintype "bidirectional"))
    )
    (net (code "233") (name "/JTAG.TCK") (class "Default")
      (node (ref "FPGA") (pin "A17") (pinfunction "TCK_A17") (pintype "input"))
    )
    (net (code "234") (name "/JTAG.TDI") (class "Default")
      (node (ref "FPGA") (pin "D15") (pinfunction "TDI_D15") (pintype "input"))
    )
    (net (code "235") (name "/JTAG.TDO") (class "Default")
      (node (ref "FPGA") (pin "D16") (pinfunction "TDO_D16") (pintype "output"))
    )
    (net (code "236") (name "/JTAG.TMS") (class "Default")
      (node (ref "FPGA") (pin "B18") (pinfunction "TMS_B18") (pintype "input"))
    )
    (net (code "238") (name "1.2V") (class "Default")
      (node (ref "FPGA") (pin "G7") (pinfunction "VCCINT_G7") (pintype "power_in"))
      (node (ref "FPGA") (pin "H11") (pinfunction "VCCINT_H11") (pintype "power_in"))
      (node (ref "FPGA") (pin "H9") (pinfunction "VCCINT_H9") (pintype "power_in"))
      (node (ref "FPGA") (pin "J10") (pinfunction "VCCINT_J10") (pintype "power_in"))
      (node (ref "FPGA") (pin "J8") (pinfunction "VCCINT_J8") (pintype "power_in"))
      (node (ref "FPGA") (pin "K11") (pinfunction "VCCINT_K11") (pintype "power_in"))
      (node (ref "FPGA") (pin "K9") (pinfunction "VCCINT_K9") (pintype "power_in"))
      (node (ref "FPGA") (pin "L10") (pinfunction "VCCINT_L10") (pintype "power_in"))
      (node (ref "FPGA") (pin "L8") (pinfunction "VCCINT_L8") (pintype "power_in"))
      (node (ref "FPGA") (pin "M12") (pinfunction "VCCINT_M12") (pintype "power_in"))
      (node (ref "FPGA") (pin "M7") (pinfunction "VCCINT_M7") (pintype "power_in"))
    )
    (net (code "239") (name "3.3V") (class "Default")
      (node (ref "FPGA") (pin "B1") (pinfunction "VCCAUX_B1") (pintype "power_in"))
      (node (ref "FPGA") (pin "B10") (pinfunction "VCCO_0_B10") (pintype "power_in"))
      (node (ref "FPGA") (pin "B15") (pinfunction "VCCO_0_B15") (pintype "power_in"))
      (node (ref "FPGA") (pin "B17") (pinfunction "VCCAUX_B17") (pintype "power_in"))
      (node (ref "FPGA") (pin "B5") (pinfunction "VCCO_0_B5") (pintype "power_in"))
      (node (ref "FPGA") (pin "D13") (pinfunction "VCCO_0_D13") (pintype "power_in"))
      (node (ref "FPGA") (pin "D7") (pinfunction "VCCO_0_D7") (pintype "power_in"))
      (node (ref "FPGA") (pin "E10") (pinfunction "VCCO_0_E10") (pintype "power_in"))
      (node (ref "FPGA") (pin "E14") (pinfunction "VCCAUX_E14") (pintype "power_in"))
      (node (ref "FPGA") (pin "E17") (pinfunction "VCCO_1_E17") (pintype "power_in"))
      (node (ref "FPGA") (pin "E2") (pinfunction "VCCO_3_E2") (pintype "power_in"))
      (node (ref "FPGA") (pin "E5") (pinfunction "VCCAUX_E5") (pintype "power_in"))
      (node (ref "FPGA") (pin "E9") (pinfunction "VCCAUX_E9") (pintype "power_in"))
      (node (ref "FPGA") (pin "G10") (pinfunction "VCCAUX_G10") (pintype "power_in"))
      (node (ref "FPGA") (pin "G15") (pinfunction "VCCO_1_G15") (pintype "power_in"))
      (node (ref "FPGA") (pin "G4") (pinfunction "VCCO_3_G4") (pintype "power_in"))
      (node (ref "FPGA") (pin "J12") (pinfunction "VCCAUX_J12") (pintype "power_in"))
      (node (ref "FPGA") (pin "J14") (pinfunction "VCCO_1_J14") (pintype "power_in"))
      (node (ref "FPGA") (pin "J17") (pinfunction "VCCO_1_J17") (pintype "power_in"))
      (node (ref "FPGA") (pin "J2") (pinfunction "VCCO_3_J2") (pintype "power_in"))
      (node (ref "FPGA") (pin "J5") (pinfunction "VCCO_3_J5") (pintype "power_in"))
      (node (ref "FPGA") (pin "K7") (pinfunction "VCCAUX_K7") (pintype "power_in"))
      (node (ref "FPGA") (pin "M15") (pinfunction "VCCO_1_M15") (pintype "power_in"))
      (node (ref "FPGA") (pin "M4") (pinfunction "VCCO_3_M4") (pintype "power_in"))
      (node (ref "FPGA") (pin "M9") (pinfunction "VCCAUX_M9") (pintype "power_in"))
      (node (ref "FPGA") (pin "P10") (pinfunction "VCCAUX_P10") (pintype "power_in"))
      (node (ref "FPGA") (pin "P14") (pinfunction "VCCAUX_P14") (pintype "power_in"))
      (node (ref "FPGA") (pin "P5") (pinfunction "VCCAUX_P5") (pintype "power_in"))
      (node (ref "FPGA") (pin "P9") (pinfunction "VCCO_2_P9") (pintype "power_in"))
      (node (ref "FPGA") (pin "R12") (pinfunction "VCCO_2_R12") (pintype "power_in"))
      (node (ref "FPGA") (pin "R17") (pinfunction "VCCO_1_R17") (pintype "power_in"))
      (node (ref "FPGA") (pin "R2") (pinfunction "VCCO_3_R2") (pintype "power_in"))
      (node (ref "FPGA") (pin "R6") (pinfunction "VCCO_2_R6") (pintype "power_in"))
      (node (ref "FPGA") (pin "U14") (pinfunction "VCCO_2_U14") (pintype "power_in"))
      (node (ref "FPGA") (pin "U4") (pinfunction "VCCO_2_U4") (pintype "power_in"))
      (node (ref "FPGA") (pin "U9") (pinfunction "VCCO_2_U9") (pintype "power_in"))
      (node (ref "R1") (pin "2") (pinfunction "2_2") (pintype "passive"))
      (node (ref "R2") (pin "2") (pinfunction "2_2") (pintype "passive"))
      (node (ref "R3") (pin "2") (pinfunction "2_2") (pintype "passive"))
    )
    (net (code "240") (name "GND") (class "Default")
      (node (ref "FPGA") (pin "A1") (pinfunction "GND_A1") (pintype "power_in"))
      (node (ref "FPGA") (pin "A18") (pinfunction "GND_A18") (pintype "power_in"))
      (node (ref "FPGA") (pin "B13") (pinfunction "GND_B13") (pintype "power_in"))
      (node (ref "FPGA") (pin "B7") (pinfunction "GND_B7") (pintype "power_in"))
      (node (ref "FPGA") (pin "C16") (pinfunction "GND_C16") (pintype "power_in"))
      (node (ref "FPGA") (pin "C3") (pinfunction "GND_C3") (pintype "power_in"))
      (node (ref "FPGA") (pin "D10") (pinfunction "GND_D10") (pintype "power_in"))
      (node (ref "FPGA") (pin "D5") (pinfunction "GND_D5") (pintype "power_in"))
      (node (ref "FPGA") (pin "E15") (pinfunction "GND_E15") (pintype "power_in"))
      (node (ref "FPGA") (pin "G12") (pinfunction "GND_G12") (pintype "power_in"))
      (node (ref "FPGA") (pin "G17") (pinfunction "GND_G17") (pintype "power_in"))
      (node (ref "FPGA") (pin "G2") (pinfunction "GND_G2") (pintype "power_in"))
      (node (ref "FPGA") (pin "G5") (pinfunction "GND_G5") (pintype "power_in"))
      (node (ref "FPGA") (pin "H10") (pinfunction "GND_H10") (pintype "power_in"))
      (node (ref "FPGA") (pin "H8") (pinfunction "GND_H8") (pintype "power_in"))
      (node (ref "FPGA") (pin "J11") (pinfunction "GND_J11") (pintype "power_in"))
      (node (ref "FPGA") (pin "J15") (pinfunction "GND_J15") (pintype "power_in"))
      (node (ref "FPGA") (pin "J4") (pinfunction "GND_J4") (pintype "power_in"))
      (node (ref "FPGA") (pin "J9") (pinfunction "GND_J9") (pintype "power_in"))
      (node (ref "FPGA") (pin "K10") (pinfunction "GND_K10") (pintype "power_in"))
      (node (ref "FPGA") (pin "K8") (pinfunction "GND_K8") (pintype "power_in"))
      (node (ref "FPGA") (pin "L11") (pinfunction "GND_L11") (pintype "power_in"))
      (node (ref "FPGA") (pin "L9") (pinfunction "GND_L9") (pintype "power_in"))
      (node (ref "FPGA") (pin "M17") (pinfunction "GND_M17") (pintype "power_in"))
      (node (ref "FPGA") (pin "M2") (pinfunction "GND_M2") (pintype "power_in"))
      (node (ref "FPGA") (pin "M6") (pinfunction "GND_M6") (pintype "power_in"))
      (node (ref "FPGA") (pin "N13") (pinfunction "GND_N13") (pintype "power_in"))
      (node (ref "FPGA") (pin "P13") (pinfunction "CMPCS_B_2_P13") (pintype "input"))
      (node (ref "FPGA") (pin "R1") (pinfunction "GND_R1") (pintype "power_in"))
      (node (ref "FPGA") (pin "R14") (pinfunction "GND_R14") (pintype "power_in"))
      (node (ref "FPGA") (pin "R16") (pinfunction "SUSPEND_R16") (pintype "input"))
      (node (ref "FPGA") (pin "R18") (pinfunction "GND_R18") (pintype "power_in"))
      (node (ref "FPGA") (pin "R4") (pinfunction "GND_R4") (pintype "power_in"))
      (node (ref "FPGA") (pin "R9") (pinfunction "GND_R9") (pintype "power_in"))
      (node (ref "FPGA") (pin "T16") (pinfunction "GND_T16") (pintype "power_in"))
      (node (ref "FPGA") (pin "U12") (pinfunction "GND_U12") (pintype "power_in"))
      (node (ref "FPGA") (pin "U6") (pinfunction "GND_U6") (pintype "power_in"))
      (node (ref "FPGA") (pin "V1") (pinfunction "GND_V1") (pintype "power_in"))
      (node (ref "FPGA") (pin "V18") (pinfunction "GND_V18") (pintype "power_in"))
    )
    (net (code "241") (name "Net-(FPGAE-DONE_2)") (class "Default")
      (node (ref "FPGA") (pin "V17") (pinfunction "DONE_2_V17") (pintype "bidirectional"))
      (node (ref "R2") (pin "1") (pinfunction "1_1") (pintype "passive"))
    )
    (net (code "242") (name "Net-(FPGAE-PROGRAM_B_2)") (class "Default")
      (node (ref "FPGA") (pin "V2") (pinfunction "PROGRAM_B_2_V2") (pintype "input"))
      (node (ref "R1") (pin "1") (pinfunction "1_1") (pintype "passive"))
    )
    (net (code "243") (name "unconnected-(FPGAC-IO_L45P_2-PadT6)") (class "Default")
      (node (ref "FPGA") (pin "T6") (pinfunction "IO_L45P_2_T6") (pintype "bidirectional"))
    )
    (net (code "244") (name "unconnected-(FPGAC-IO_L64N_D9_2-PadP6)") (class "Default")
      (node (ref "FPGA") (pin "P6") (pinfunction "IO_L64N_D9_2_P6") (pintype "bidirectional"))
    )
    (net (code "245") (name "unconnected-(FPGAH-NC-PadC12)") (class "Default")
      (node (ref "FPGA") (pin "C12") (pinfunction "NC_C12") (pintype "passive"))
    )
    (net (code "246") (name "unconnected-(FPGAH-NC-PadD12)") (class "Default")
      (node (ref "FPGA") (pin "D12") (pinfunction "NC_D12") (pintype "passive"))
    )
    (net (code "247") (name "unconnected-(FPGAH-NC-PadE6)") (class "Default")
      (node (ref "FPGA") (pin "E6") (pinfunction "NC_E6") (pintype "passive"))
    )
    (net (code "248") (name "unconnected-(FPGAH-NC-PadE7)") (class "Default")
      (node (ref "FPGA") (pin "E7") (pinfunction "NC_E7") (pintype "passive"))
    )
    (net (code "249") (name "unconnected-(FPGAH-NC-PadE8)") (class "Default")
      (node (ref "FPGA") (pin "E8") (pinfunction "NC_E8") (pintype "passive"))
    )
    (net (code "250") (name "unconnected-(FPGAH-NC-PadE11)") (class "Default")
      (node (ref "FPGA") (pin "E11") (pinfunction "NC_E11") (pintype "passive"))
    )
    (net (code "251") (name "unconnected-(FPGAH-NC-PadE12)") (class "Default")
      (node (ref "FPGA") (pin "E12") (pinfunction "NC_E12") (pintype "passive"))
    )
    (net (code "252") (name "unconnected-(FPGAH-NC-PadF7)") (class "Default")
      (node (ref "FPGA") (pin "F7") (pinfunction "NC_F7") (pintype "passive"))
    )
    (net (code "253") (name "unconnected-(FPGAH-NC-PadF8)") (class "Default")
      (node (ref "FPGA") (pin "F8") (pinfunction "NC_F8") (pintype "passive"))
    )
    (net (code "254") (name "unconnected-(FPGAH-NC-PadF10)") (class "Default")
      (node (ref "FPGA") (pin "F10") (pinfunction "NC_F10") (pintype "passive"))
    )
    (net (code "255") (name "unconnected-(FPGAH-NC-PadF11)") (class "Default")
      (node (ref "FPGA") (pin "F11") (pinfunction "NC_F11") (pintype "passive"))
    )
    (net (code "256") (name "unconnected-(FPGAH-NC-PadF12)") (class "Default")
      (node (ref "FPGA") (pin "F12") (pinfunction "NC_F12") (pintype "passive"))
    )
    (net (code "257") (name "unconnected-(FPGAH-NC-PadG8)") (class "Default")
      (node (ref "FPGA") (pin "G8") (pinfunction "NC_G8") (pintype "passive"))
    )
    (net (code "258") (name "unconnected-(FPGAH-NC-PadG11)") (class "Default")
      (node (ref "FPGA") (pin "G11") (pinfunction "NC_G11") (pintype "passive"))
    )
  )
)
